# Buck_Regulator.net
KiCad netlist of a schematic drawn in Altium Designer
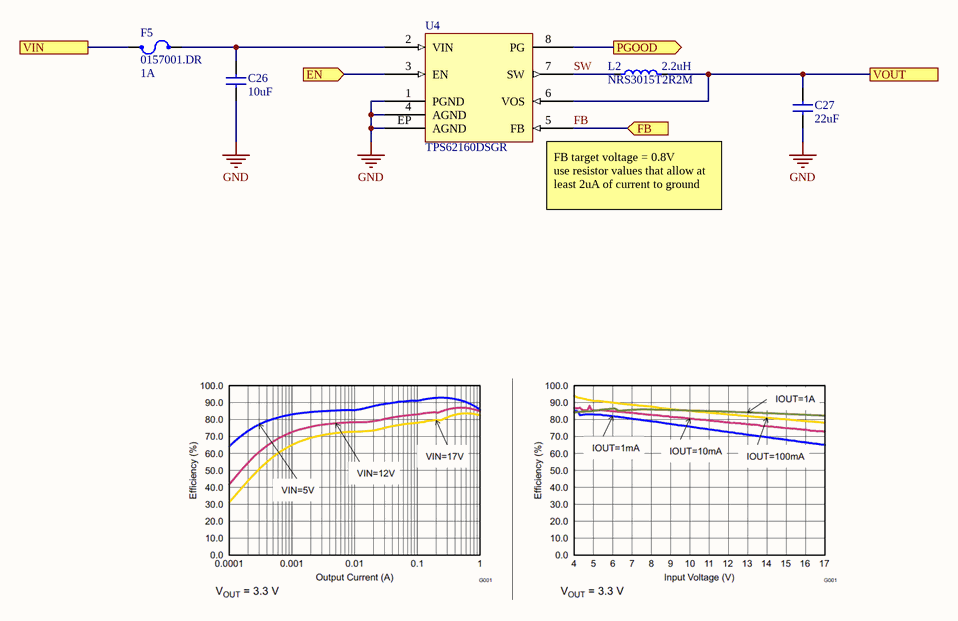
[diagram p0: Buck_Regulator.SchDoc]

(export (version "E")
  (design (tool "Eeschema 10.0.6"))
  (components
    (comp (ref "C26")
      (value "10uF")
      (footprint "1206_CAPACITOR")
      (description "CAP CERM 10uF 20% 50V 1206")
      (fields
        (field (name "VOLTAGE") "50V")
        (field (name "Comment") "CAP 10uF 50V X5R")
        (field (name "SVP CREATOR") "Spencer Berglund")
      )
      (libsource (lib "capacitor") (part "C_1206_10uF_50V_20%"))
    )
    (comp (ref "C27")
      (value "22uF")
      (footprint "0805_Capacitor")
      (description "CAP CERM 22uF 20% 16V 0805")
      (fields (field (name "VOLTAGE") "16V") (field (name "Comment") "CAP 22uF 16V X5R"))
      (libsource (lib "capacitor") (part "C_0805_22uF_16V_20%"))
    )
    (comp (ref "F5")
      (value "0157001.DR")
      (footprint "F_157T")
      (description "FUSE BRD MNT 1A 125VAC/VDC 2SMD")
      (fields (field (name "MANUFACTURER") "Littelfuse") (field (name "ALTIUM_VALUE") "1A"))
      (libsource (lib "fuse") (part "F_0157001.DR"))
    )
    (comp (ref "L2")
      (value "NRS3015T2R2M")
      (footprint "L_NRS_Series_3.0x3.0mm")
      (fields
        (field (name "TOLERANCE") "20%")
        (field (name "MANUFACTURER PART NUMBER") "NRS3015T2R2MNGH")
        (field (name "MANUFACTURER") "Taiyo Yuden")
        (field (name "ALTIUM_VALUE") "2.2uH")
      )
      (libsource (lib "inductor") (part "L_NRS3015T2R2M"))
    )
    (comp (ref "U4")
      (value "TPS62160DSGR")
      (footprint "WFDFN-8-EP")
      (description "Buck Switching Regulator IC Positive Adjustable 0.9V 1 Output 1A")
      (libsource (lib "ic") (part "U_TPS62160"))
    )
  )
  (nets
    (net (code "1") (name "/EN") (class "Default")
      (node (ref "U4") (pin "3") (pinfunction "EN_3") (pintype "input"))
    )
    (net (code "2") (name "/FB") (class "Default")
      (node (ref "U4") (pin "5") (pinfunction "FB_5") (pintype "input"))
    )
    (net (code "3") (name "/PGOOD") (class "Default")
      (node (ref "U4") (pin "8") (pinfunction "PG_8") (pintype "open_collector"))
    )
    (net (code "4") (name "/SW") (class "Default")
      (node (ref "L2") (pin "1") (pinfunction "1_1") (pintype "passive"))
      (node (ref "U4") (pin "7") (pinfunction "SW_7") (pintype "output"))
    )
    (net (code "5") (name "/VIN") (class "Default")
      (node (ref "F5") (pin "1") (pinfunction "1_1") (pintype "passive"))
    )
    (net (code "6") (name "/VOUT") (class "Default")
      (node (ref "C27") (pin "1") (pinfunction "1_1") (pintype "passive"))
      (node (ref "L2") (pin "2") (pinfunction "2_2") (pintype "passive"))
      (node (ref "U4") (pin "6") (pinfunction "VOS_6") (pintype "input"))
    )
    (net (code "7") (name "GND") (class "Default")
      (node (ref "C26") (pin "2") (pinfunction "2_2") (pintype "passive"))
      (node (ref "C27") (pin "2") (pinfunction "2_2") (pintype "passive"))
      (node (ref "U4") (pin "1") (pinfunction "PGND_1") (pintype "power_in"))
      (node (ref "U4") (pin "4") (pinfunction "AGND_4") (pintype "power_in"))
      (node (ref "U4") (pin "EP") (pinfunction "AGND_EP") (pintype "power_in"))
    )
    (net (code "8") (name "Net-(U4-VIN)") (class "Default")
      (node (ref "C26") (pin "1") (pinfunction "1_1") (pintype "passive"))
      (node (ref "F5") (pin "2") (pinfunction "2_2") (pintype "passive"))
      (node (ref "U4") (pin "2") (pinfunction "VIN_2") (pintype "input"))
    )
  )
)
